# LoadCell.net
KiCad netlist of a schematic drawn in Altium Designer
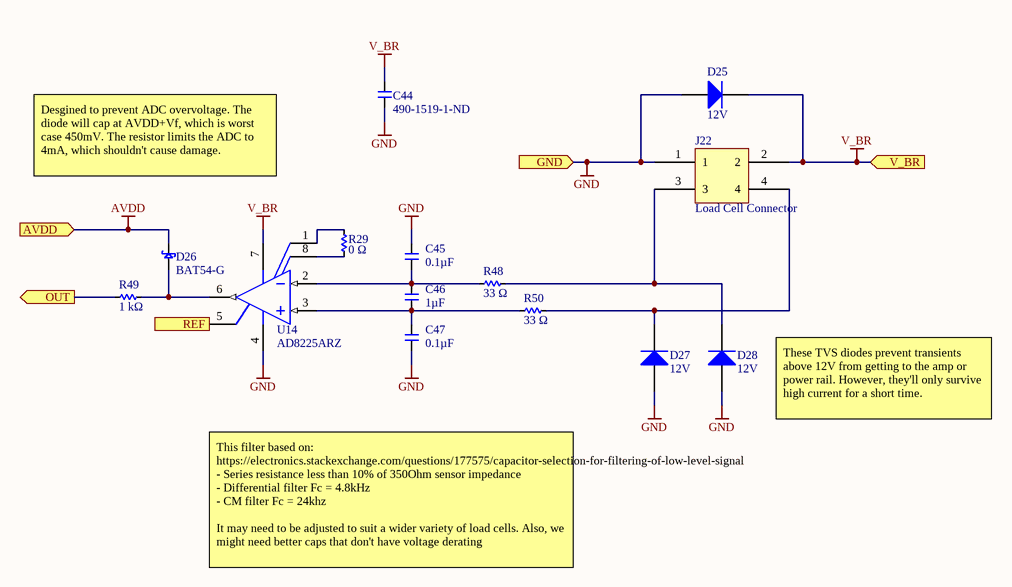
[diagram p0: LoadCell.SchDoc]

(export (version "E")
  (design (tool "Eeschema 10.0.6"))
  (components
    (comp (ref "C44")
      (value "490-1519-1-ND")
      (footprint "C0603")
      (description "CAP CER 0603 0.1µF X7R 50V 10%")
      (fields (field (name "MANUFACTURER") "Murata Electronics North America"))
      (libsource (lib "Stanford Student Space Initiative") (part "__template_cap"))
    )
    (comp (ref "C45")
      (value "CAP_CER_100NF_100V")
      (footprint "C0603")
      (description "CAP CER 0.1UF 100V X7S 0603")
      (fields
        (field (name "MANUFACTURER") "TDK Corporation")
        (field (name "TOLERANCE") "±10%")
        (field (name "CAPACITANCE") "0.1µF")
      )
      (libsource (lib "Stanford Student Space Initiative") (part "Symbol"))
    )
    (comp (ref "C46")
      (value "490-3900-1-ND")
      (footprint "C0603")
      (description "CAP CER 0603 1µF X7R 16V 10%")
      (fields
        (field (name "MANUFACTURER") "Murata Electronics North America")
        (field (name "CAPACITANCE (SHORTHAND)") "1µF")
      )
      (libsource (lib "Stanford Student Space Initiative") (part "__template_cap"))
    )
    (comp (ref "C47")
      (value "CAP_CER_100NF_100V")
      (footprint "C0603")
      (description "CAP CER 0.1UF 100V X7S 0603")
      (fields
        (field (name "MANUFACTURER") "TDK Corporation")
        (field (name "TOLERANCE") "±10%")
        (field (name "CAPACITANCE") "0.1µF")
      )
      (libsource (lib "Stanford Student Space Initiative") (part "Symbol"))
    )
    (comp (ref "D25")
      (value "SMAJ12A-E3/61")
      (footprint "VISH-DO-214AC-2_M")
      (fields (field (name "REVERSE STANDOFF VOLTAGE") "12V") (field (name "VOLTAGE") "12V"))
      (libsource (lib "Stanford Student Space Initiative") (part "VISH-K1A2-2"))
    )
    (comp (ref "D26")
      (value "SCHOTTKY_BAT54-G")
      (footprint "3SOT23")
      (description "DIODE SCHOTTKY 200MA 30V SOT-23")
      (fields
        (field (name "MANUFACTURER PART NUMBER") "BAT54-G")
        (field (name "MANUFACTURER") "Comchip Technology")
      )
      (libsource (lib "Stanford Student Space Initiative") (part "SCHOTTKY_BAT54-G"))
    )
    (comp (ref "D27")
      (value "SMAJ12A-E3/61")
      (footprint "VISH-DO-214AC-2_M")
      (fields (field (name "REVERSE STANDOFF VOLTAGE") "12V") (field (name "VOLTAGE") "12V"))
      (libsource (lib "Stanford Student Space Initiative") (part "VISH-K1A2-2"))
    )
    (comp (ref "D28")
      (value "SMAJ12A-E3/61")
      (footprint "VISH-DO-214AC-2_M")
      (fields (field (name "REVERSE STANDOFF VOLTAGE") "12V") (field (name "VOLTAGE") "12V"))
      (libsource (lib "Stanford Student Space Initiative") (part "VISH-K1A2-2"))
    )
    (comp (ref "J22")
      (value "Load Cell Connector")
      (footprint "MOLEX_2x2_0430450400")
      (description "MICROFIT CONN HEADER R/A 4POS 3MM")
      (libsource (lib "Stanford Student Space Initiative") (part "MOLEX_2x2_0430450400"))
    )
    (comp (ref "R29")
      (value "311-0.0HRCT-ND")
      (footprint "R0603")
      (description "RES SMD 0 OHM JUMPER 1/10W 0603")
      (fields
        (field (name "TOLERANCE") "Jumper")
        (field (name "MANUFACTURER") "Yageo")
        (field (name "RESISTANCE") "0 Ω")
      )
      (libsource (lib "Stanford Student Space Initiative") (part "__template_resistor"))
    )
    (comp (ref "R48")
      (value "311-33.0HRCT-ND")
      (footprint "R0603")
      (description "RES SMD 33 OHM 1% 1/10W 0603")
      (fields
        (field (name "TOLERANCE") "±1%")
        (field (name "MANUFACTURER PART NUMBER") "RC0603FR-0733RL")
        (field (name "RESISTANCE") "33 Ω")
      )
      (libsource (lib "Stanford Student Space Initiative") (part "__template_resistor"))
    )
    (comp (ref "R49")
      (value "311-1.00KHRCT-ND")
      (footprint "R0603")
      (description "RES SMD 1K OHM 1% 1/10W 0603")
      (fields
        (field (name "TOLERANCE") "±1%")
        (field (name "MANUFACTURER PART NUMBER") "RC0603FR-071KL")
        (field (name "RESISTANCE") "1 kΩ")
      )
      (libsource (lib "Stanford Student Space Initiative") (part "__template_resistor"))
    )
    (comp (ref "R50")
      (value "311-33.0HRCT-ND")
      (footprint "R0603")
      (description "RES SMD 33 OHM 1% 1/10W 0603")
      (fields
        (field (name "TOLERANCE") "±1%")
        (field (name "MANUFACTURER PART NUMBER") "RC0603FR-0733RL")
        (field (name "RESISTANCE") "33 Ω")
      )
      (libsource (lib "Stanford Student Space Initiative") (part "__template_resistor"))
    )
    (comp (ref "U14")
      (value "AD8225ARZ")
      (footprint "ADI-R-8_N")
      (description "SP Amp INSTR Amp Single ±18V/36V 8-Pin SOIC N Tube")
      (libsource (lib "Stanford Student Space Initiative") (part "ADI-AD8225-8"))
    )
  )
  (nets
    (net (code "1") (name "/OUT") (class "Default")
      (node (ref "R49") (pin "1") (pinfunction "1_1") (pintype "passive"))
    )
    (net (code "2") (name "/REF") (class "Default")
      (node (ref "U14") (pin "5") (pinfunction "REF_5") (pintype "passive"))
    )
    (net (code "3") (name "AVDD") (class "Default") (node (ref "D26") (pin "3") (pintype "passive")))
    (net (code "4") (name "GND") (class "Default")
      (node (ref "C44") (pin "2") (pintype "passive"))
      (node (ref "C45") (pin "1") (pintype "passive"))
      (node (ref "C47") (pin "2") (pintype "passive"))
      (node (ref "D25") (pin "2") (pinfunction "A_2") (pintype "passive"))
      (node (ref "D27") (pin "2") (pinfunction "A_2") (pintype "passive"))
      (node (ref "D28") (pin "2") (pinfunction "A_2") (pintype "passive"))
      (node (ref "J22") (pin "1") (pinfunction "1_1") (pintype "passive"))
      (node (ref "U14") (pin "4") (pinfunction "VS-_4") (pintype "power_in"))
    )
    (net (code "5") (name "Net-(D27-K)") (class "Default")
      (node (ref "D27") (pin "1") (pinfunction "K_1") (pintype "passive"))
      (node (ref "J22") (pin "4") (pinfunction "4_4") (pintype "passive"))
      (node (ref "R50") (pin "2") (pinfunction "2_2") (pintype "passive"))
    )
    (net (code "6") (name "Net-(D28-K)") (class "Default")
      (node (ref "D28") (pin "1") (pinfunction "K_1") (pintype "passive"))
      (node (ref "J22") (pin "3") (pinfunction "3_3") (pintype "passive"))
      (node (ref "R48") (pin "2") (pinfunction "2_2") (pintype "passive"))
    )
    (net (code "7") (name "Net-(R29-Pad1)") (class "Default")
      (node (ref "R29") (pin "1") (pinfunction "1_1") (pintype "passive"))
      (node (ref "U14") (pin "8") (pinfunction "NC_8") (pintype "passive"))
    )
    (net (code "8") (name "Net-(R29-Pad2)") (class "Default")
      (node (ref "R29") (pin "2") (pinfunction "2_2") (pintype "passive"))
      (node (ref "U14") (pin "1") (pinfunction "NC_1") (pintype "passive"))
    )
    (net (code "9") (name "Net-(U14-IN+)") (class "Default")
      (node (ref "C46") (pin "2") (pintype "passive"))
      (node (ref "C47") (pin "1") (pintype "passive"))
      (node (ref "R50") (pin "1") (pinfunction "1_1") (pintype "passive"))
      (node (ref "U14") (pin "3") (pinfunction "IN+_3") (pintype "input"))
    )
    (net (code "10") (name "Net-(U14-IN-)") (class "Default")
      (node (ref "C45") (pin "2") (pintype "passive"))
      (node (ref "C46") (pin "1") (pintype "passive"))
      (node (ref "R48") (pin "1") (pinfunction "1_1") (pintype "passive"))
      (node (ref "U14") (pin "2") (pinfunction "IN-_2") (pintype "input"))
    )
    (net (code "11") (name "Net-(U14-VOUT)") (class "Default")
      (node (ref "D26") (pin "1") (pintype "passive"))
      (node (ref "R49") (pin "2") (pinfunction "2_2") (pintype "passive"))
      (node (ref "U14") (pin "6") (pinfunction "VOUT_6") (pintype "output"))
    )
    (net (code "12") (name "V_BR") (class "Default")
      (node (ref "C44") (pin "1") (pintype "passive"))
      (node (ref "D25") (pin "1") (pinfunction "K_1") (pintype "passive"))
      (node (ref "J22") (pin "2") (pinfunction "2_2") (pintype "passive"))
      (node (ref "U14") (pin "7") (pinfunction "VS+_7") (pintype "power_in"))
    )
  )
)
